# internal_breakout.net
KiCad netlist of a schematic drawn in EAGLE
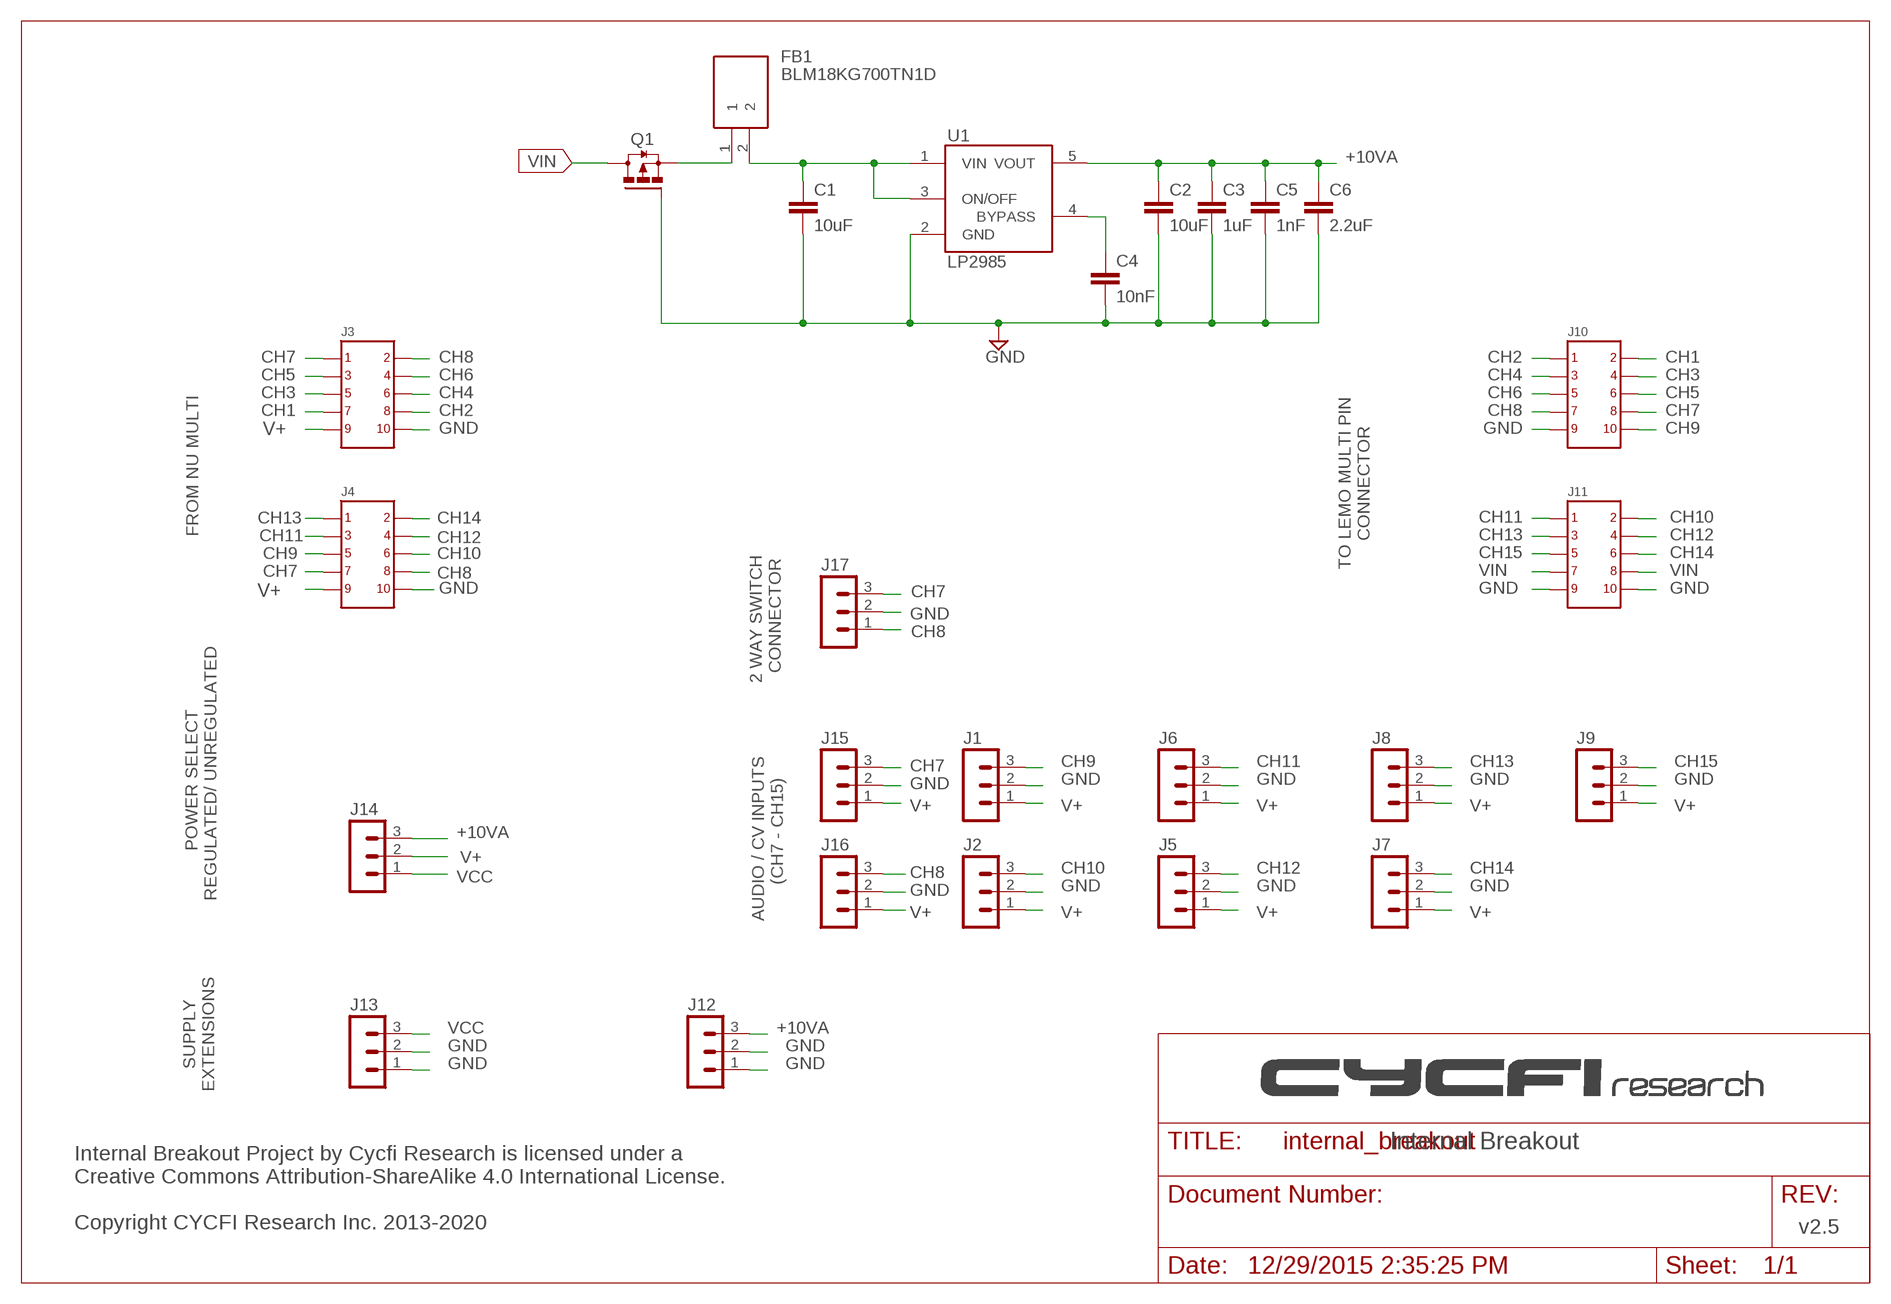
[diagram p0: schematic, sheet 1]

(export (version "E")
  (design (tool "Eeschema 10.0.6"))
  (components
    (comp (ref "C1")
      (value "10uF")
      (footprint "eagle-import:C0603")
      (fields (field (name "SPICEPREFIX") "C"))
      (libsource (lib "eagle-import") (part "C-EUC0603"))
    )
    (comp (ref "C2")
      (value "10uF")
      (footprint "eagle-import:C0603")
      (libsource (lib "eagle-import") (part "C-EUC0603"))
    )
    (comp (ref "C3")
      (value "1uF")
      (footprint "eagle-import:C0603")
      (libsource (lib "eagle-import") (part "C-EUC0603"))
    )
    (comp (ref "C4")
      (value "10nF")
      (footprint "eagle-import:C0402")
      (libsource (lib "eagle-import") (part "C-EUC0402"))
    )
    (comp (ref "C5")
      (value "1nF")
      (footprint "eagle-import:C0402")
      (libsource (lib "eagle-import") (part "C-EUC0402"))
    )
    (comp (ref "C6")
      (value "2.2uF")
      (footprint "eagle-import:C0603")
      (libsource (lib "eagle-import") (part "C-EUC0603"))
    )
    (comp (ref "FB1")
      (value "BLM18KG700TN1D")
      (footprint "eagle-import:BEADC1608X75N")
      (fields (field (name "MOUSER_PART_NUMBER") "81-BLM18KG700TN1D"))
      (libsource (lib "eagle-import") (part "BLM18KG700TN1D"))
    )
    (comp (ref "J1")
      (value "MA03-1")
      (footprint "eagle-import:MA03-1")
      (libsource (lib "eagle-import") (part "MA03-1"))
    )
    (comp (ref "J2")
      (value "MA03-1")
      (footprint "eagle-import:MA03-1")
      (libsource (lib "eagle-import") (part "MA03-1"))
    )
    (comp (ref "J3")
      (value "2X5")
      (footprint "eagle-import:2X5")
      (libsource (lib "eagle-import") (part "2X5"))
    )
    (comp (ref "J4")
      (value "2X5")
      (footprint "eagle-import:2X5")
      (libsource (lib "eagle-import") (part "2X5"))
    )
    (comp (ref "J5")
      (value "MA03-1")
      (footprint "eagle-import:MA03-1")
      (libsource (lib "eagle-import") (part "MA03-1"))
    )
    (comp (ref "J6")
      (value "MA03-1")
      (footprint "eagle-import:MA03-1")
      (libsource (lib "eagle-import") (part "MA03-1"))
    )
    (comp (ref "J7")
      (value "MA03-1")
      (footprint "eagle-import:MA03-1")
      (libsource (lib "eagle-import") (part "MA03-1"))
    )
    (comp (ref "J8")
      (value "MA03-1")
      (footprint "eagle-import:MA03-1")
      (libsource (lib "eagle-import") (part "MA03-1"))
    )
    (comp (ref "J9")
      (value "MA03-1")
      (footprint "eagle-import:MA03-1")
      (libsource (lib "eagle-import") (part "MA03-1"))
    )
    (comp (ref "J10")
      (value "2X5")
      (footprint "eagle-import:2X5")
      (libsource (lib "eagle-import") (part "2X5"))
    )
    (comp (ref "J11")
      (value "2X5")
      (footprint "eagle-import:2X5")
      (libsource (lib "eagle-import") (part "2X5"))
    )
    (comp (ref "J12")
      (value "MA03-1")
      (footprint "eagle-import:MA03-1")
      (libsource (lib "eagle-import") (part "MA03-1"))
    )
    (comp (ref "J13")
      (value "MA03-1")
      (footprint "eagle-import:MA03-1")
      (libsource (lib "eagle-import") (part "MA03-1"))
    )
    (comp (ref "J14")
      (value "MA03-1")
      (footprint "eagle-import:MA03-1")
      (libsource (lib "eagle-import") (part "MA03-1"))
    )
    (comp (ref "J15")
      (value "MA03-1")
      (footprint "eagle-import:MA03-1")
      (fields (field (name "OC_FARNELL") "unknown") (field (name "OC_NEWARK") "unknown"))
      (libsource (lib "eagle-import") (part "MA03-1"))
    )
    (comp (ref "J16")
      (value "MA03-1")
      (footprint "eagle-import:MA03-1")
      (fields (field (name "OC_FARNELL") "unknown") (field (name "OC_NEWARK") "unknown"))
      (libsource (lib "eagle-import") (part "MA03-1"))
    )
    (comp (ref "J17")
      (value "MA03-1")
      (footprint "eagle-import:MA03-1")
      (fields (field (name "OC_FARNELL") "unknown") (field (name "OC_NEWARK") "unknown"))
      (libsource (lib "eagle-import") (part "MA03-1"))
    )
    (comp (ref "Q1")
      (value "DMP3099L")
      (footprint "eagle-import:SUPER-SOT3")
      (libsource (lib "eagle-import") (part "FDN360P"))
    )
    (comp (ref "U1")
      (value "LP2985")
      (footprint "eagle-import:SOT25")
      (libsource (lib "eagle-import") (part "LP2985AIM5-3.3"))
    )
  )
  (nets
    (net (code "1") (name "/+10VA") (class "Default")
      (node (ref "C2") (pin "1") (pinfunction "1_1") (pintype "passive"))
      (node (ref "C3") (pin "1") (pinfunction "1_1") (pintype "passive"))
      (node (ref "C5") (pin "1") (pinfunction "1_1") (pintype "passive"))
      (node (ref "C6") (pin "1") (pinfunction "1_1") (pintype "passive"))
      (node (ref "J12") (pin "3") (pinfunction "3_3") (pintype "passive"))
      (node (ref "J14") (pin "3") (pinfunction "3_3") (pintype "passive"))
      (node (ref "U1") (pin "5") (pinfunction "VOUT_5") (pintype "power_in"))
    )
    (net (code "2") (name "/CH1") (class "Default")
      (node (ref "J10") (pin "2") (pinfunction "2_2") (pintype "bidirectional"))
      (node (ref "J3") (pin "7") (pinfunction "7_7") (pintype "bidirectional"))
    )
    (net (code "3") (name "/CH2") (class "Default")
      (node (ref "J10") (pin "1") (pinfunction "1_1") (pintype "bidirectional"))
      (node (ref "J3") (pin "8") (pinfunction "8_8") (pintype "bidirectional"))
    )
    (net (code "4") (name "/CH3") (class "Default")
      (node (ref "J10") (pin "4") (pinfunction "4_4") (pintype "bidirectional"))
      (node (ref "J3") (pin "5") (pinfunction "5_5") (pintype "bidirectional"))
    )
    (net (code "5") (name "/CH4") (class "Default")
      (node (ref "J10") (pin "3") (pinfunction "3_3") (pintype "bidirectional"))
      (node (ref "J3") (pin "6") (pinfunction "6_6") (pintype "bidirectional"))
    )
    (net (code "6") (name "/CH5") (class "Default")
      (node (ref "J10") (pin "6") (pinfunction "6_6") (pintype "bidirectional"))
      (node (ref "J3") (pin "3") (pinfunction "3_3") (pintype "bidirectional"))
    )
    (net (code "7") (name "/CH6") (class "Default")
      (node (ref "J10") (pin "5") (pinfunction "5_5") (pintype "bidirectional"))
      (node (ref "J3") (pin "4") (pinfunction "4_4") (pintype "bidirectional"))
    )
    (net (code "8") (name "/CH7") (class "Default")
      (node (ref "J10") (pin "8") (pinfunction "8_8") (pintype "bidirectional"))
      (node (ref "J15") (pin "3") (pinfunction "3_3") (pintype "passive"))
      (node (ref "J17") (pin "3") (pinfunction "3_3") (pintype "passive"))
      (node (ref "J3") (pin "1") (pinfunction "1_1") (pintype "bidirectional"))
      (node (ref "J4") (pin "7") (pinfunction "7_7") (pintype "bidirectional"))
    )
    (net (code "9") (name "/CH8") (class "Default")
      (node (ref "J10") (pin "7") (pinfunction "7_7") (pintype "bidirectional"))
      (node (ref "J16") (pin "3") (pinfunction "3_3") (pintype "passive"))
      (node (ref "J17") (pin "1") (pinfunction "1_1") (pintype "passive"))
      (node (ref "J3") (pin "2") (pinfunction "2_2") (pintype "bidirectional"))
      (node (ref "J4") (pin "8") (pinfunction "8_8") (pintype "bidirectional"))
    )
    (net (code "10") (name "/CH9") (class "Default")
      (node (ref "J1") (pin "3") (pinfunction "3_3") (pintype "passive"))
      (node (ref "J10") (pin "10") (pinfunction "10_10") (pintype "bidirectional"))
      (node (ref "J4") (pin "5") (pinfunction "5_5") (pintype "bidirectional"))
    )
    (net (code "11") (name "/CH10") (class "Default")
      (node (ref "J11") (pin "2") (pinfunction "2_2") (pintype "bidirectional"))
      (node (ref "J2") (pin "3") (pinfunction "3_3") (pintype "passive"))
      (node (ref "J4") (pin "6") (pinfunction "6_6") (pintype "bidirectional"))
    )
    (net (code "12") (name "/CH11") (class "Default")
      (node (ref "J11") (pin "1") (pinfunction "1_1") (pintype "bidirectional"))
      (node (ref "J4") (pin "3") (pinfunction "3_3") (pintype "bidirectional"))
      (node (ref "J6") (pin "3") (pinfunction "3_3") (pintype "passive"))
    )
    (net (code "13") (name "/CH12") (class "Default")
      (node (ref "J11") (pin "4") (pinfunction "4_4") (pintype "bidirectional"))
      (node (ref "J4") (pin "4") (pinfunction "4_4") (pintype "bidirectional"))
      (node (ref "J5") (pin "3") (pinfunction "3_3") (pintype "passive"))
    )
    (net (code "14") (name "/CH13") (class "Default")
      (node (ref "J11") (pin "3") (pinfunction "3_3") (pintype "bidirectional"))
      (node (ref "J4") (pin "1") (pinfunction "1_1") (pintype "bidirectional"))
      (node (ref "J8") (pin "3") (pinfunction "3_3") (pintype "passive"))
    )
    (net (code "15") (name "/CH14") (class "Default")
      (node (ref "J11") (pin "6") (pinfunction "6_6") (pintype "bidirectional"))
      (node (ref "J4") (pin "2") (pinfunction "2_2") (pintype "bidirectional"))
      (node (ref "J7") (pin "3") (pinfunction "3_3") (pintype "passive"))
    )
    (net (code "16") (name "/CH15") (class "Default")
      (node (ref "J11") (pin "5") (pinfunction "5_5") (pintype "bidirectional"))
      (node (ref "J9") (pin "3") (pinfunction "3_3") (pintype "passive"))
    )
    (net (code "17") (name "/V+") (class "Default")
      (node (ref "J1") (pin "1") (pinfunction "1_1") (pintype "passive"))
      (node (ref "J14") (pin "2") (pinfunction "2_2") (pintype "passive"))
      (node (ref "J15") (pin "1") (pinfunction "1_1") (pintype "passive"))
      (node (ref "J16") (pin "1") (pinfunction "1_1") (pintype "passive"))
      (node (ref "J2") (pin "1") (pinfunction "1_1") (pintype "passive"))
      (node (ref "J3") (pin "9") (pinfunction "9_9") (pintype "bidirectional"))
      (node (ref "J4") (pin "9") (pinfunction "9_9") (pintype "bidirectional"))
      (node (ref "J5") (pin "1") (pinfunction "1_1") (pintype "passive"))
      (node (ref "J6") (pin "1") (pinfunction "1_1") (pintype "passive"))
      (node (ref "J7") (pin "1") (pinfunction "1_1") (pintype "passive"))
      (node (ref "J8") (pin "1") (pinfunction "1_1") (pintype "passive"))
      (node (ref "J9") (pin "1") (pinfunction "1_1") (pintype "passive"))
    )
    (net (code "18") (name "/VCC") (class "Default")
      (node (ref "C1") (pin "1") (pinfunction "1_1") (pintype "passive"))
      (node (ref "FB1") (pin "2") (pinfunction "2_2") (pintype "bidirectional"))
      (node (ref "J13") (pin "3") (pinfunction "3_3") (pintype "passive"))
      (node (ref "J14") (pin "1") (pinfunction "1_1") (pintype "passive"))
      (node (ref "U1") (pin "1") (pinfunction "VIN_1") (pintype "power_in"))
      (node (ref "U1") (pin "3") (pinfunction "ON/OFF_3") (pintype "input"))
    )
    (net (code "19") (name "/VIN") (class "Default")
      (node (ref "J11") (pin "7") (pinfunction "7_7") (pintype "bidirectional"))
      (node (ref "J11") (pin "8") (pinfunction "8_8") (pintype "bidirectional"))
      (node (ref "Q1") (pin "3") (pinfunction "D_3") (pintype "passive"))
    )
    (net (code "20") (name "GND") (class "Default")
      (node (ref "C1") (pin "2") (pinfunction "2_2") (pintype "passive"))
      (node (ref "C2") (pin "2") (pinfunction "2_2") (pintype "passive"))
      (node (ref "C3") (pin "2") (pinfunction "2_2") (pintype "passive"))
      (node (ref "C4") (pin "2") (pinfunction "2_2") (pintype "passive"))
      (node (ref "C5") (pin "2") (pinfunction "2_2") (pintype "passive"))
      (node (ref "C6") (pin "2") (pinfunction "2_2") (pintype "passive"))
      (node (ref "J1") (pin "2") (pinfunction "2_2") (pintype "passive"))
      (node (ref "J10") (pin "9") (pinfunction "9_9") (pintype "bidirectional"))
      (node (ref "J11") (pin "10") (pinfunction "10_10") (pintype "bidirectional"))
      (node (ref "J11") (pin "9") (pinfunction "9_9") (pintype "bidirectional"))
      (node (ref "J12") (pin "1") (pinfunction "1_1") (pintype "passive"))
      (node (ref "J12") (pin "2") (pinfunction "2_2") (pintype "passive"))
      (node (ref "J13") (pin "1") (pinfunction "1_1") (pintype "passive"))
      (node (ref "J13") (pin "2") (pinfunction "2_2") (pintype "passive"))
      (node (ref "J15") (pin "2") (pinfunction "2_2") (pintype "passive"))
      (node (ref "J16") (pin "2") (pinfunction "2_2") (pintype "passive"))
      (node (ref "J17") (pin "2") (pinfunction "2_2") (pintype "passive"))
      (node (ref "J2") (pin "2") (pinfunction "2_2") (pintype "passive"))
      (node (ref "J3") (pin "10") (pinfunction "10_10") (pintype "bidirectional"))
      (node (ref "J4") (pin "10") (pinfunction "10_10") (pintype "bidirectional"))
      (node (ref "J5") (pin "2") (pinfunction "2_2") (pintype "passive"))
      (node (ref "J6") (pin "2") (pinfunction "2_2") (pintype "passive"))
      (node (ref "J7") (pin "2") (pinfunction "2_2") (pintype "passive"))
      (node (ref "J8") (pin "2") (pinfunction "2_2") (pintype "passive"))
      (node (ref "J9") (pin "2") (pinfunction "2_2") (pintype "passive"))
      (node (ref "Q1") (pin "1") (pinfunction "G_1") (pintype "passive"))
      (node (ref "U1") (pin "2") (pinfunction "GND_2") (pintype "power_in"))
    )
    (net (code "21") (name "Net-(Q1-S)") (class "Default")
      (node (ref "FB1") (pin "1") (pinfunction "1_1") (pintype "bidirectional"))
      (node (ref "Q1") (pin "2") (pinfunction "S_2") (pintype "passive"))
    )
    (net (code "22") (name "Net-(U1-BYPASS)") (class "Default")
      (node (ref "C4") (pin "1") (pinfunction "1_1") (pintype "passive"))
      (node (ref "U1") (pin "4") (pinfunction "BYPASS_4") (pintype "power_in"))
    )
  )
)
